# 4_Mosfet.net
KiCad netlist of a schematic drawn in Altium Designer
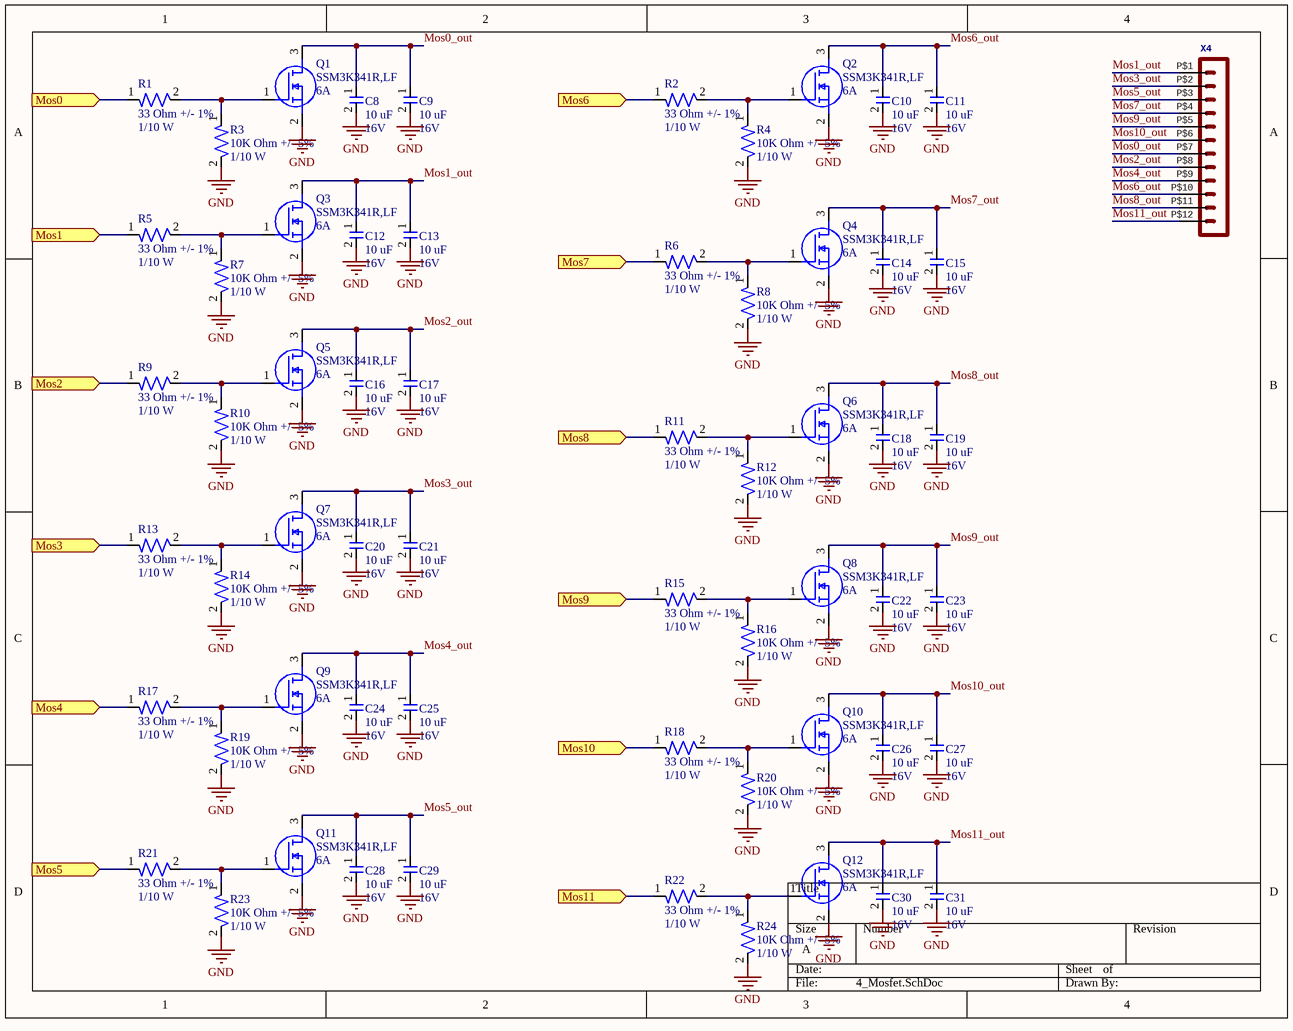
[diagram p0: 4_Mosfet.SchDoc]

(export (version "E")
  (design (tool "Eeschema 10.0.6"))
  (components
    (comp (ref "C8")
      (value "CL21A106KOQNNNE")
      (footprint "CAP-0805")
      (description "10 µF ±10% 16V Ceramic Capacitor X7R 0805 (2012 Metric)")
      (fields (field (name "CAPACITANCE") "10 uF") (field (name "VOLTAGE RATING") "16V"))
      (libsource (lib "MasterLib") (part "CAP-10U-0002"))
    )
    (comp (ref "C9")
      (value "CL21A106KOQNNNE")
      (footprint "CAP-0805")
      (description "10 µF ±10% 16V Ceramic Capacitor X7R 0805 (2012 Metric)")
      (fields (field (name "CAPACITANCE") "10 uF") (field (name "VOLTAGE RATING") "16V"))
      (libsource (lib "MasterLib") (part "CAP-10U-0002"))
    )
    (comp (ref "C10")
      (value "CL21A106KOQNNNE")
      (footprint "CAP-0805")
      (description "10 µF ±10% 16V Ceramic Capacitor X7R 0805 (2012 Metric)")
      (fields (field (name "CAPACITANCE") "10 uF") (field (name "VOLTAGE RATING") "16V"))
      (libsource (lib "MasterLib") (part "CAP-10U-0002"))
    )
    (comp (ref "C11")
      (value "CL21A106KOQNNNE")
      (footprint "CAP-0805")
      (description "10 µF ±10% 16V Ceramic Capacitor X7R 0805 (2012 Metric)")
      (fields (field (name "CAPACITANCE") "10 uF") (field (name "VOLTAGE RATING") "16V"))
      (libsource (lib "MasterLib") (part "CAP-10U-0002"))
    )
    (comp (ref "C12")
      (value "CL21A106KOQNNNE")
      (footprint "CAP-0805")
      (description "10 µF ±10% 16V Ceramic Capacitor X7R 0805 (2012 Metric)")
      (fields (field (name "CAPACITANCE") "10 uF") (field (name "VOLTAGE RATING") "16V"))
      (libsource (lib "MasterLib") (part "CAP-10U-0002"))
    )
    (comp (ref "C13")
      (value "CL21A106KOQNNNE")
      (footprint "CAP-0805")
      (description "10 µF ±10% 16V Ceramic Capacitor X7R 0805 (2012 Metric)")
      (fields (field (name "CAPACITANCE") "10 uF") (field (name "VOLTAGE RATING") "16V"))
      (libsource (lib "MasterLib") (part "CAP-10U-0002"))
    )
    (comp (ref "C14")
      (value "CL21A106KOQNNNE")
      (footprint "CAP-0805")
      (description "10 µF ±10% 16V Ceramic Capacitor X7R 0805 (2012 Metric)")
      (fields (field (name "CAPACITANCE") "10 uF") (field (name "VOLTAGE RATING") "16V"))
      (libsource (lib "MasterLib") (part "CAP-10U-0002"))
    )
    (comp (ref "C15")
      (value "CL21A106KOQNNNE")
      (footprint "CAP-0805")
      (description "10 µF ±10% 16V Ceramic Capacitor X7R 0805 (2012 Metric)")
      (fields (field (name "CAPACITANCE") "10 uF") (field (name "VOLTAGE RATING") "16V"))
      (libsource (lib "MasterLib") (part "CAP-10U-0002"))
    )
    (comp (ref "C16")
      (value "CL21A106KOQNNNE")
      (footprint "CAP-0805")
      (description "10 µF ±10% 16V Ceramic Capacitor X7R 0805 (2012 Metric)")
      (fields (field (name "CAPACITANCE") "10 uF") (field (name "VOLTAGE RATING") "16V"))
      (libsource (lib "MasterLib") (part "CAP-10U-0002"))
    )
    (comp (ref "C17")
      (value "CL21A106KOQNNNE")
      (footprint "CAP-0805")
      (description "10 µF ±10% 16V Ceramic Capacitor X7R 0805 (2012 Metric)")
      (fields (field (name "CAPACITANCE") "10 uF") (field (name "VOLTAGE RATING") "16V"))
      (libsource (lib "MasterLib") (part "CAP-10U-0002"))
    )
    (comp (ref "C18")
      (value "CL21A106KOQNNNE")
      (footprint "CAP-0805")
      (description "10 µF ±10% 16V Ceramic Capacitor X7R 0805 (2012 Metric)")
      (fields (field (name "CAPACITANCE") "10 uF") (field (name "VOLTAGE RATING") "16V"))
      (libsource (lib "MasterLib") (part "CAP-10U-0002"))
    )
    (comp (ref "C19")
      (value "CL21A106KOQNNNE")
      (footprint "CAP-0805")
      (description "10 µF ±10% 16V Ceramic Capacitor X7R 0805 (2012 Metric)")
      (fields (field (name "CAPACITANCE") "10 uF") (field (name "VOLTAGE RATING") "16V"))
      (libsource (lib "MasterLib") (part "CAP-10U-0002"))
    )
    (comp (ref "C20")
      (value "CL21A106KOQNNNE")
      (footprint "CAP-0805")
      (description "10 µF ±10% 16V Ceramic Capacitor X7R 0805 (2012 Metric)")
      (fields (field (name "CAPACITANCE") "10 uF") (field (name "VOLTAGE RATING") "16V"))
      (libsource (lib "MasterLib") (part "CAP-10U-0002"))
    )
    (comp (ref "C21")
      (value "CL21A106KOQNNNE")
      (footprint "CAP-0805")
      (description "10 µF ±10% 16V Ceramic Capacitor X7R 0805 (2012 Metric)")
      (fields (field (name "CAPACITANCE") "10 uF") (field (name "VOLTAGE RATING") "16V"))
      (libsource (lib "MasterLib") (part "CAP-10U-0002"))
    )
    (comp (ref "C22")
      (value "CL21A106KOQNNNE")
      (footprint "CAP-0805")
      (description "10 µF ±10% 16V Ceramic Capacitor X7R 0805 (2012 Metric)")
      (fields (field (name "CAPACITANCE") "10 uF") (field (name "VOLTAGE RATING") "16V"))
      (libsource (lib "MasterLib") (part "CAP-10U-0002"))
    )
    (comp (ref "C23")
      (value "CL21A106KOQNNNE")
      (footprint "CAP-0805")
      (description "10 µF ±10% 16V Ceramic Capacitor X7R 0805 (2012 Metric)")
      (fields (field (name "CAPACITANCE") "10 uF") (field (name "VOLTAGE RATING") "16V"))
      (libsource (lib "MasterLib") (part "CAP-10U-0002"))
    )
    (comp (ref "C24")
      (value "CL21A106KOQNNNE")
      (footprint "CAP-0805")
      (description "10 µF ±10% 16V Ceramic Capacitor X7R 0805 (2012 Metric)")
      (fields (field (name "CAPACITANCE") "10 uF") (field (name "VOLTAGE RATING") "16V"))
      (libsource (lib "MasterLib") (part "CAP-10U-0002"))
    )
    (comp (ref "C25")
      (value "CL21A106KOQNNNE")
      (footprint "CAP-0805")
      (description "10 µF ±10% 16V Ceramic Capacitor X7R 0805 (2012 Metric)")
      (fields (field (name "CAPACITANCE") "10 uF") (field (name "VOLTAGE RATING") "16V"))
      (libsource (lib "MasterLib") (part "CAP-10U-0002"))
    )
    (comp (ref "C26")
      (value "CL21A106KOQNNNE")
      (footprint "CAP-0805")
      (description "10 µF ±10% 16V Ceramic Capacitor X7R 0805 (2012 Metric)")
      (fields (field (name "CAPACITANCE") "10 uF") (field (name "VOLTAGE RATING") "16V"))
      (libsource (lib "MasterLib") (part "CAP-10U-0002"))
    )
    (comp (ref "C27")
      (value "CL21A106KOQNNNE")
      (footprint "CAP-0805")
      (description "10 µF ±10% 16V Ceramic Capacitor X7R 0805 (2012 Metric)")
      (fields (field (name "CAPACITANCE") "10 uF") (field (name "VOLTAGE RATING") "16V"))
      (libsource (lib "MasterLib") (part "CAP-10U-0002"))
    )
    (comp (ref "C28")
      (value "CL21A106KOQNNNE")
      (footprint "CAP-0805")
      (description "10 µF ±10% 16V Ceramic Capacitor X7R 0805 (2012 Metric)")
      (fields (field (name "CAPACITANCE") "10 uF") (field (name "VOLTAGE RATING") "16V"))
      (libsource (lib "MasterLib") (part "CAP-10U-0002"))
    )
    (comp (ref "C29")
      (value "CL21A106KOQNNNE")
      (footprint "CAP-0805")
      (description "10 µF ±10% 16V Ceramic Capacitor X7R 0805 (2012 Metric)")
      (fields (field (name "CAPACITANCE") "10 uF") (field (name "VOLTAGE RATING") "16V"))
      (libsource (lib "MasterLib") (part "CAP-10U-0002"))
    )
    (comp (ref "C30")
      (value "CL21A106KOQNNNE")
      (footprint "CAP-0805")
      (description "10 µF ±10% 16V Ceramic Capacitor X7R 0805 (2012 Metric)")
      (fields (field (name "CAPACITANCE") "10 uF") (field (name "VOLTAGE RATING") "16V"))
      (libsource (lib "MasterLib") (part "CAP-10U-0002"))
    )
    (comp (ref "C31")
      (value "CL21A106KOQNNNE")
      (footprint "CAP-0805")
      (description "10 µF ±10% 16V Ceramic Capacitor X7R 0805 (2012 Metric)")
      (fields (field (name "CAPACITANCE") "10 uF") (field (name "VOLTAGE RATING") "16V"))
      (libsource (lib "MasterLib") (part "CAP-10U-0002"))
    )
    (comp (ref "Q1")
      (value "SSM3K341R,LF")
      (footprint "NMOS-SOT23-3")
      (description "N-Channel 60 V 6A (Ta) 1.2W (Ta) Surface Mount SOT-23F")
      (fields (field (name "ID") "6A"))
      (libsource (lib "MasterLib") (part "NMOS-5A-0001"))
    )
    (comp (ref "Q2")
      (value "SSM3K341R,LF")
      (footprint "NMOS-SOT23-3")
      (description "N-Channel 60 V 6A (Ta) 1.2W (Ta) Surface Mount SOT-23F")
      (fields (field (name "ID") "6A"))
      (libsource (lib "MasterLib") (part "NMOS-5A-0001"))
    )
    (comp (ref "Q3")
      (value "SSM3K341R,LF")
      (footprint "NMOS-SOT23-3")
      (description "N-Channel 60 V 6A (Ta) 1.2W (Ta) Surface Mount SOT-23F")
      (fields (field (name "ID") "6A"))
      (libsource (lib "MasterLib") (part "NMOS-5A-0001"))
    )
    (comp (ref "Q4")
      (value "SSM3K341R,LF")
      (footprint "NMOS-SOT23-3")
      (description "N-Channel 60 V 6A (Ta) 1.2W (Ta) Surface Mount SOT-23F")
      (fields (field (name "ID") "6A"))
      (libsource (lib "MasterLib") (part "NMOS-5A-0001"))
    )
    (comp (ref "Q5")
      (value "SSM3K341R,LF")
      (footprint "NMOS-SOT23-3")
      (description "N-Channel 60 V 6A (Ta) 1.2W (Ta) Surface Mount SOT-23F")
      (fields (field (name "ID") "6A"))
      (libsource (lib "MasterLib") (part "NMOS-5A-0001"))
    )
    (comp (ref "Q6")
      (value "SSM3K341R,LF")
      (footprint "NMOS-SOT23-3")
      (description "N-Channel 60 V 6A (Ta) 1.2W (Ta) Surface Mount SOT-23F")
      (fields (field (name "ID") "6A"))
      (libsource (lib "MasterLib") (part "NMOS-5A-0001"))
    )
    (comp (ref "Q7")
      (value "SSM3K341R,LF")
      (footprint "NMOS-SOT23-3")
      (description "N-Channel 60 V 6A (Ta) 1.2W (Ta) Surface Mount SOT-23F")
      (fields (field (name "ID") "6A"))
      (libsource (lib "MasterLib") (part "NMOS-5A-0001"))
    )
    (comp (ref "Q8")
      (value "SSM3K341R,LF")
      (footprint "NMOS-SOT23-3")
      (description "N-Channel 60 V 6A (Ta) 1.2W (Ta) Surface Mount SOT-23F")
      (fields (field (name "ID") "6A"))
      (libsource (lib "MasterLib") (part "NMOS-5A-0001"))
    )
    (comp (ref "Q9")
      (value "SSM3K341R,LF")
      (footprint "NMOS-SOT23-3")
      (description "N-Channel 60 V 6A (Ta) 1.2W (Ta) Surface Mount SOT-23F")
      (fields (field (name "ID") "6A"))
      (libsource (lib "MasterLib") (part "NMOS-5A-0001"))
    )
    (comp (ref "Q10")
      (value "SSM3K341R,LF")
      (footprint "NMOS-SOT23-3")
      (description "N-Channel 60 V 6A (Ta) 1.2W (Ta) Surface Mount SOT-23F")
      (fields (field (name "ID") "6A"))
      (libsource (lib "MasterLib") (part "NMOS-5A-0001"))
    )
    (comp (ref "Q11")
      (value "SSM3K341R,LF")
      (footprint "NMOS-SOT23-3")
      (description "N-Channel 60 V 6A (Ta) 1.2W (Ta) Surface Mount SOT-23F")
      (fields (field (name "ID") "6A"))
      (libsource (lib "MasterLib") (part "NMOS-5A-0001"))
    )
    (comp (ref "Q12")
      (value "SSM3K341R,LF")
      (footprint "NMOS-SOT23-3")
      (description "N-Channel 60 V 6A (Ta) 1.2W (Ta) Surface Mount SOT-23F")
      (fields (field (name "ID") "6A"))
      (libsource (lib "MasterLib") (part "NMOS-5A-0001"))
    )
    (comp (ref "R1")
      (value "ERJ2RKF33R0X")
      (footprint "RES-0402")
      (description "100mW Thick Film Resistors ±100ppm/℃ ±1% -55℃~+155℃ 33Ω 0402  Chip Resistor - Surface Mount ROHS")
      (fields
        (field (name "RESISTANCE") "33 Ohm +/- 1%")
        (field (name "POWER") "1/10 W")
        (field (name "JLC PART NUMBER") "C278594")
      )
      (libsource (lib "MasterLib") (part "RES-33-0003-JLC"))
    )
    (comp (ref "R2")
      (value "ERJ2RKF33R0X")
      (footprint "RES-0402")
      (description "100mW Thick Film Resistors ±100ppm/℃ ±1% -55℃~+155℃ 33Ω 0402  Chip Resistor - Surface Mount ROHS")
      (fields
        (field (name "RESISTANCE") "33 Ohm +/- 1%")
        (field (name "POWER") "1/10 W")
        (field (name "JLC PART NUMBER") "C278594")
      )
      (libsource (lib "MasterLib") (part "RES-33-0003-JLC"))
    )
    (comp (ref "R3")
      (value "ERJ2GEJ103X")
      (footprint "RES-0402")
      (fields
        (field (name "RESISTANCE") "10K Ohm +/- 5%")
        (field (name "POWER") "1/10 W")
        (field (name "JLC PART NUMBER") "C278577")
      )
      (libsource (lib "MasterLib") (part "RES-10K-0003-JLC"))
    )
    (comp (ref "R4")
      (value "ERJ2GEJ103X")
      (footprint "RES-0402")
      (fields
        (field (name "RESISTANCE") "10K Ohm +/- 5%")
        (field (name "POWER") "1/10 W")
        (field (name "JLC PART NUMBER") "C278577")
      )
      (libsource (lib "MasterLib") (part "RES-10K-0003-JLC"))
    )
    (comp (ref "R5")
      (value "ERJ2RKF33R0X")
      (footprint "RES-0402")
      (description "100mW Thick Film Resistors ±100ppm/℃ ±1% -55℃~+155℃ 33Ω 0402  Chip Resistor - Surface Mount ROHS")
      (fields
        (field (name "RESISTANCE") "33 Ohm +/- 1%")
        (field (name "POWER") "1/10 W")
        (field (name "JLC PART NUMBER") "C278594")
      )
      (libsource (lib "MasterLib") (part "RES-33-0003-JLC"))
    )
    (comp (ref "R6")
      (value "ERJ2RKF33R0X")
      (footprint "RES-0402")
      (description "100mW Thick Film Resistors ±100ppm/℃ ±1% -55℃~+155℃ 33Ω 0402  Chip Resistor - Surface Mount ROHS")
      (fields
        (field (name "RESISTANCE") "33 Ohm +/- 1%")
        (field (name "POWER") "1/10 W")
        (field (name "JLC PART NUMBER") "C278594")
      )
      (libsource (lib "MasterLib") (part "RES-33-0003-JLC"))
    )
    (comp (ref "R7")
      (value "ERJ2GEJ103X")
      (footprint "RES-0402")
      (fields
        (field (name "RESISTANCE") "10K Ohm +/- 5%")
        (field (name "POWER") "1/10 W")
        (field (name "JLC PART NUMBER") "C278577")
      )
      (libsource (lib "MasterLib") (part "RES-10K-0003-JLC"))
    )
    (comp (ref "R8")
      (value "ERJ2GEJ103X")
      (footprint "RES-0402")
      (fields
        (field (name "RESISTANCE") "10K Ohm +/- 5%")
        (field (name "POWER") "1/10 W")
        (field (name "JLC PART NUMBER") "C278577")
      )
      (libsource (lib "MasterLib") (part "RES-10K-0003-JLC"))
    )
    (comp (ref "R9")
      (value "ERJ2RKF33R0X")
      (footprint "RES-0402")
      (description "100mW Thick Film Resistors ±100ppm/℃ ±1% -55℃~+155℃ 33Ω 0402  Chip Resistor - Surface Mount ROHS")
      (fields
        (field (name "RESISTANCE") "33 Ohm +/- 1%")
        (field (name "POWER") "1/10 W")
        (field (name "JLC PART NUMBER") "C278594")
      )
      (libsource (lib "MasterLib") (part "RES-33-0003-JLC"))
    )
    (comp (ref "R10")
      (value "ERJ2GEJ103X")
      (footprint "RES-0402")
      (fields
        (field (name "RESISTANCE") "10K Ohm +/- 5%")
        (field (name "POWER") "1/10 W")
        (field (name "JLC PART NUMBER") "C278577")
      )
      (libsource (lib "MasterLib") (part "RES-10K-0003-JLC"))
    )
    (comp (ref "R11")
      (value "ERJ2RKF33R0X")
      (footprint "RES-0402")
      (description "100mW Thick Film Resistors ±100ppm/℃ ±1% -55℃~+155℃ 33Ω 0402  Chip Resistor - Surface Mount ROHS")
      (fields
        (field (name "RESISTANCE") "33 Ohm +/- 1%")
        (field (name "POWER") "1/10 W")
        (field (name "JLC PART NUMBER") "C278594")
      )
      (libsource (lib "MasterLib") (part "RES-33-0003-JLC"))
    )
    (comp (ref "R12")
      (value "ERJ2GEJ103X")
      (footprint "RES-0402")
      (fields
        (field (name "RESISTANCE") "10K Ohm +/- 5%")
        (field (name "POWER") "1/10 W")
        (field (name "JLC PART NUMBER") "C278577")
      )
      (libsource (lib "MasterLib") (part "RES-10K-0003-JLC"))
    )
    (comp (ref "R13")
      (value "ERJ2RKF33R0X")
      (footprint "RES-0402")
      (description "100mW Thick Film Resistors ±100ppm/℃ ±1% -55℃~+155℃ 33Ω 0402  Chip Resistor - Surface Mount ROHS")
      (fields
        (field (name "RESISTANCE") "33 Ohm +/- 1%")
        (field (name "POWER") "1/10 W")
        (field (name "JLC PART NUMBER") "C278594")
      )
      (libsource (lib "MasterLib") (part "RES-33-0003-JLC"))
    )
    (comp (ref "R14")
      (value "ERJ2GEJ103X")
      (footprint "RES-0402")
      (fields
        (field (name "RESISTANCE") "10K Ohm +/- 5%")
        (field (name "POWER") "1/10 W")
        (field (name "JLC PART NUMBER") "C278577")
      )
      (libsource (lib "MasterLib") (part "RES-10K-0003-JLC"))
    )
    (comp (ref "R15")
      (value "ERJ2RKF33R0X")
      (footprint "RES-0402")
      (description "100mW Thick Film Resistors ±100ppm/℃ ±1% -55℃~+155℃ 33Ω 0402  Chip Resistor - Surface Mount ROHS")
      (fields
        (field (name "RESISTANCE") "33 Ohm +/- 1%")
        (field (name "POWER") "1/10 W")
        (field (name "JLC PART NUMBER") "C278594")
      )
      (libsource (lib "MasterLib") (part "RES-33-0003-JLC"))
    )
    (comp (ref "R16")
      (value "ERJ2GEJ103X")
      (footprint "RES-0402")
      (fields
        (field (name "RESISTANCE") "10K Ohm +/- 5%")
        (field (name "POWER") "1/10 W")
        (field (name "JLC PART NUMBER") "C278577")
      )
      (libsource (lib "MasterLib") (part "RES-10K-0003-JLC"))
    )
    (comp (ref "R17")
      (value "ERJ2RKF33R0X")
      (footprint "RES-0402")
      (description "100mW Thick Film Resistors ±100ppm/℃ ±1% -55℃~+155℃ 33Ω 0402  Chip Resistor - Surface Mount ROHS")
      (fields
        (field (name "RESISTANCE") "33 Ohm +/- 1%")
        (field (name "POWER") "1/10 W")
        (field (name "JLC PART NUMBER") "C278594")
      )
      (libsource (lib "MasterLib") (part "RES-33-0003-JLC"))
    )
    (comp (ref "R18")
      (value "ERJ2RKF33R0X")
      (footprint "RES-0402")
      (description "100mW Thick Film Resistors ±100ppm/℃ ±1% -55℃~+155℃ 33Ω 0402  Chip Resistor - Surface Mount ROHS")
      (fields
        (field (name "RESISTANCE") "33 Ohm +/- 1%")
        (field (name "POWER") "1/10 W")
        (field (name "JLC PART NUMBER") "C278594")
      )
      (libsource (lib "MasterLib") (part "RES-33-0003-JLC"))
    )
    (comp (ref "R19")
      (value "ERJ2GEJ103X")
      (footprint "RES-0402")
      (fields
        (field (name "RESISTANCE") "10K Ohm +/- 5%")
        (field (name "POWER") "1/10 W")
        (field (name "JLC PART NUMBER") "C278577")
      )
      (libsource (lib "MasterLib") (part "RES-10K-0003-JLC"))
    )
    (comp (ref "R20")
      (value "ERJ2GEJ103X")
      (footprint "RES-0402")
      (fields
        (field (name "RESISTANCE") "10K Ohm +/- 5%")
        (field (name "POWER") "1/10 W")
        (field (name "JLC PART NUMBER") "C278577")
      )
      (libsource (lib "MasterLib") (part "RES-10K-0003-JLC"))
    )
    (comp (ref "R21")
      (value "ERJ2RKF33R0X")
      (footprint "RES-0402")
      (description "100mW Thick Film Resistors ±100ppm/℃ ±1% -55℃~+155℃ 33Ω 0402  Chip Resistor - Surface Mount ROHS")
      (fields
        (field (name "RESISTANCE") "33 Ohm +/- 1%")
        (field (name "POWER") "1/10 W")
        (field (name "JLC PART NUMBER") "C278594")
      )
      (libsource (lib "MasterLib") (part "RES-33-0003-JLC"))
    )
    (comp (ref "R22")
      (value "ERJ2RKF33R0X")
      (footprint "RES-0402")
      (description "100mW Thick Film Resistors ±100ppm/℃ ±1% -55℃~+155℃ 33Ω 0402  Chip Resistor - Surface Mount ROHS")
      (fields
        (field (name "RESISTANCE") "33 Ohm +/- 1%")
        (field (name "POWER") "1/10 W")
        (field (name "JLC PART NUMBER") "C278594")
      )
      (libsource (lib "MasterLib") (part "RES-33-0003-JLC"))
    )
    (comp (ref "R23")
      (value "ERJ2GEJ103X")
      (footprint "RES-0402")
      (fields
        (field (name "RESISTANCE") "10K Ohm +/- 5%")
        (field (name "POWER") "1/10 W")
        (field (name "JLC PART NUMBER") "C278577")
      )
      (libsource (lib "MasterLib") (part "RES-10K-0003-JLC"))
    )
    (comp (ref "R24")
      (value "ERJ2GEJ103X")
      (footprint "RES-0402")
      (fields
        (field (name "RESISTANCE") "10K Ohm +/- 5%")
        (field (name "POWER") "1/10 W")
        (field (name "JLC PART NUMBER") "C278577")
      )
      (libsource (lib "MasterLib") (part "RES-10K-0003-JLC"))
    )
    (comp (ref "X4")
      (value "Molex - Micro-Fit 3.0 Series connector,  3.00mm (0.118\") pitch header, 12 positions.")
      (footprint "43045-1212")
      (libsource (lib "Molex Microfit") (part "HEADER_POS12_?43045-1212"))
    )
  )
  (nets
    (net (code "1") (name "/Mos0") (class "Default")
      (node (ref "R1") (pin "1") (pinfunction "1_1") (pintype "passive"))
    )
    (net (code "2") (name "/Mos0_out") (class "Default")
      (node (ref "C8") (pin "1") (pinfunction "1_1") (pintype "passive"))
      (node (ref "C9") (pin "1") (pinfunction "1_1") (pintype "passive"))
      (node (ref "Q1") (pin "3") (pinfunction "D_3") (pintype "passive"))
      (node (ref "X4") (pin "P$7") (pinfunction "7_P$7") (pintype "passive"))
    )
    (net (code "3") (name "/Mos1") (class "Default")
      (node (ref "R5") (pin "1") (pinfunction "1_1") (pintype "passive"))
    )
    (net (code "4") (name "/Mos1_out") (class "Default")
      (node (ref "C12") (pin "1") (pinfunction "1_1") (pintype "passive"))
      (node (ref "C13") (pin "1") (pinfunction "1_1") (pintype "passive"))
      (node (ref "Q3") (pin "3") (pinfunction "D_3") (pintype "passive"))
      (node (ref "X4") (pin "P$1") (pinfunction "1_P$1") (pintype "passive"))
    )
    (net (code "5") (name "/Mos2") (class "Default")
      (node (ref "R9") (pin "1") (pinfunction "1_1") (pintype "passive"))
    )
    (net (code "6") (name "/Mos2_out") (class "Default")
      (node (ref "C16") (pin "1") (pinfunction "1_1") (pintype "passive"))
      (node (ref "C17") (pin "1") (pinfunction "1_1") (pintype "passive"))
      (node (ref "Q5") (pin "3") (pinfunction "D_3") (pintype "passive"))
      (node (ref "X4") (pin "P$8") (pinfunction "8_P$8") (pintype "passive"))
    )
    (net (code "7") (name "/Mos3") (class "Default")
      (node (ref "R13") (pin "1") (pinfunction "1_1") (pintype "passive"))
    )
    (net (code "8") (name "/Mos3_out") (class "Default")
      (node (ref "C20") (pin "1") (pinfunction "1_1") (pintype "passive"))
      (node (ref "C21") (pin "1") (pinfunction "1_1") (pintype "passive"))
      (node (ref "Q7") (pin "3") (pinfunction "D_3") (pintype "passive"))
      (node (ref "X4") (pin "P$2") (pinfunction "2_P$2") (pintype "passive"))
    )
    (net (code "9") (name "/Mos4") (class "Default")
      (node (ref "R17") (pin "1") (pinfunction "1_1") (pintype "passive"))
    )
    (net (code "10") (name "/Mos4_out") (class "Default")
      (node (ref "C24") (pin "1") (pinfunction "1_1") (pintype "passive"))
      (node (ref "C25") (pin "1") (pinfunction "1_1") (pintype "passive"))
      (node (ref "Q9") (pin "3") (pinfunction "D_3") (pintype "passive"))
      (node (ref "X4") (pin "P$9") (pinfunction "9_P$9") (pintype "passive"))
    )
    (net (code "11") (name "/Mos5") (class "Default")
      (node (ref "R21") (pin "1") (pinfunction "1_1") (pintype "passive"))
    )
    (net (code "12") (name "/Mos5_out") (class "Default")
      (node (ref "C28") (pin "1") (pinfunction "1_1") (pintype "passive"))
      (node (ref "C29") (pin "1") (pinfunction "1_1") (pintype "passive"))
      (node (ref "Q11") (pin "3") (pinfunction "D_3") (pintype "passive"))
      (node (ref "X4") (pin "P$3") (pinfunction "3_P$3") (pintype "passive"))
    )
    (net (code "13") (name "/Mos6") (class "Default")
      (node (ref "R2") (pin "1") (pinfunction "1_1") (pintype "passive"))
    )
    (net (code "14") (name "/Mos6_out") (class "Default")
      (node (ref "C10") (pin "1") (pinfunction "1_1") (pintype "passive"))
      (node (ref "C11") (pin "1") (pinfunction "1_1") (pintype "passive"))
      (node (ref "Q2") (pin "3") (pinfunction "D_3") (pintype "passive"))
      (node (ref "X4") (pin "P$10") (pinfunction "10_P$10") (pintype "passive"))
    )
    (net (code "15") (name "/Mos7") (class "Default")
      (node (ref "R6") (pin "1") (pinfunction "1_1") (pintype "passive"))
    )
    (net (code "16") (name "/Mos7_out") (class "Default")
      (node (ref "C14") (pin "1") (pinfunction "1_1") (pintype "passive"))
      (node (ref "C15") (pin "1") (pinfunction "1_1") (pintype "passive"))
      (node (ref "Q4") (pin "3") (pinfunction "D_3") (pintype "passive"))
      (node (ref "X4") (pin "P$4") (pinfunction "4_P$4") (pintype "passive"))
    )
    (net (code "17") (name "/Mos8") (class "Default")
      (node (ref "R11") (pin "1") (pinfunction "1_1") (pintype "passive"))
    )
    (net (code "18") (name "/Mos8_out") (class "Default")
      (node (ref "C18") (pin "1") (pinfunction "1_1") (pintype "passive"))
      (node (ref "C19") (pin "1") (pinfunction "1_1") (pintype "passive"))
      (node (ref "Q6") (pin "3") (pinfunction "D_3") (pintype "passive"))
      (node (ref "X4") (pin "P$11") (pinfunction "11_P$11") (pintype "passive"))
    )
    (net (code "19") (name "/Mos9") (class "Default")
      (node (ref "R15") (pin "1") (pinfunction "1_1") (pintype "passive"))
    )
    (net (code "20") (name "/Mos9_out") (class "Default")
      (node (ref "C22") (pin "1") (pinfunction "1_1") (pintype "passive"))
      (node (ref "C23") (pin "1") (pinfunction "1_1") (pintype "passive"))
      (node (ref "Q8") (pin "3") (pinfunction "D_3") (pintype "passive"))
      (node (ref "X4") (pin "P$5") (pinfunction "5_P$5") (pintype "passive"))
    )
    (net (code "21") (name "/Mos10") (class "Default")
      (node (ref "R18") (pin "1") (pinfunction "1_1") (pintype "passive"))
    )
    (net (code "22") (name "/Mos10_out") (class "Default")
      (node (ref "C26") (pin "1") (pinfunction "1_1") (pintype "passive"))
      (node (ref "C27") (pin "1") (pinfunction "1_1") (pintype "passive"))
      (node (ref "Q10") (pin "3") (pinfunction "D_3") (pintype "passive"))
      (node (ref "X4") (pin "P$6") (pinfunction "6_P$6") (pintype "passive"))
    )
    (net (code "23") (name "/Mos11") (class "Default")
      (node (ref "R22") (pin "1") (pinfunction "1_1") (pintype "passive"))
    )
    (net (code "24") (name "/Mos11_out") (class "Default")
      (node (ref "C30") (pin "1") (pinfunction "1_1") (pintype "passive"))
      (node (ref "C31") (pin "1") (pinfunction "1_1") (pintype "passive"))
      (node (ref "Q12") (pin "3") (pinfunction "D_3") (pintype "passive"))
      (node (ref "X4") (pin "P$12") (pinfunction "12_P$12") (pintype "passive"))
    )
    (net (code "25") (name "GND") (class "Default")
      (node (ref "C10") (pin "2") (pinfunction "2_2") (pintype "passive"))
      (node (ref "C11") (pin "2") (pinfunction "2_2") (pintype "passive"))
      (node (ref "C12") (pin "2") (pinfunction "2_2") (pintype "passive"))
      (node (ref "C13") (pin "2") (pinfunction "2_2") (pintype "passive"))
      (node (ref "C14") (pin "2") (pinfunction "2_2") (pintype "passive"))
      (node (ref "C15") (pin "2") (pinfunction "2_2") (pintype "passive"))
      (node (ref "C16") (pin "2") (pinfunction "2_2") (pintype "passive"))
      (node (ref "C17") (pin "2") (pinfunction "2_2") (pintype "passive"))
      (node (ref "C18") (pin "2") (pinfunction "2_2") (pintype "passive"))
      (node (ref "C19") (pin "2") (pinfunction "2_2") (pintype "passive"))
      (node (ref "C20") (pin "2") (pinfunction "2_2") (pintype "passive"))
      (node (ref "C21") (pin "2") (pinfunction "2_2") (pintype "passive"))
      (node (ref "C22") (pin "2") (pinfunction "2_2") (pintype "passive"))
      (node (ref "C23") (pin "2") (pinfunction "2_2") (pintype "passive"))
      (node (ref "C24") (pin "2") (pinfunction "2_2") (pintype "passive"))
      (node (ref "C25") (pin "2") (pinfunction "2_2") (pintype "passive"))
      (node (ref "C26") (pin "2") (pinfunction "2_2") (pintype "passive"))
      (node (ref "C27") (pin "2") (pinfunction "2_2") (pintype "passive"))
      (node (ref "C28") (pin "2") (pinfunction "2_2") (pintype "passive"))
      (node (ref "C29") (pin "2") (pinfunction "2_2") (pintype "passive"))
      (node (ref "C30") (pin "2") (pinfunction "2_2") (pintype "passive"))
      (node (ref "C31") (pin "2") (pinfunction "2_2") (pintype "passive"))
      (node (ref "C8") (pin "2") (pinfunction "2_2") (pintype "passive"))
      (node (ref "C9") (pin "2") (pinfunction "2_2") (pintype "passive"))
      (node (ref "Q1") (pin "2") (pinfunction "S_2") (pintype "passive"))
      (node (ref "Q10") (pin "2") (pinfunction "S_2") (pintype "passive"))
      (node (ref "Q11") (pin "2") (pinfunction "S_2") (pintype "passive"))
      (node (ref "Q12") (pin "2") (pinfunction "S_2") (pintype "passive"))
      (node (ref "Q2") (pin "2") (pinfunction "S_2") (pintype "passive"))
      (node (ref "Q3") (pin "2") (pinfunction "S_2") (pintype "passive"))
      (node (ref "Q4") (pin "2") (pinfunction "S_2") (pintype "passive"))
      (node (ref "Q5") (pin "2") (pinfunction "S_2") (pintype "passive"))
      (node (ref "Q6") (pin "2") (pinfunction "S_2") (pintype "passive"))
      (node (ref "Q7") (pin "2") (pinfunction "S_2") (pintype "passive"))
      (node (ref "Q8") (pin "2") (pinfunction "S_2") (pintype "passive"))
      (node (ref "Q9") (pin "2") (pinfunction "S_2") (pintype "passive"))
      (node (ref "R10") (pin "2") (pinfunction "2_2") (pintype "passive"))
      (node (ref "R12") (pin "2") (pinfunction "2_2") (pintype "passive"))
      (node (ref "R14") (pin "2") (pinfunction "2_2") (pintype "passive"))
      (node (ref "R16") (pin "2") (pinfunction "2_2") (pintype "passive"))
      (node (ref "R19") (pin "2") (pinfunction "2_2") (pintype "passive"))
      (node (ref "R20") (pin "2") (pinfunction "2_2") (pintype "passive"))
      (node (ref "R23") (pin "2") (pinfunction "2_2") (pintype "passive"))
      (node (ref "R24") (pin "2") (pinfunction "2_2") (pintype "passive"))
      (node (ref "R3") (pin "2") (pinfunction "2_2") (pintype "passive"))
      (node (ref "R4") (pin "2") (pinfunction "2_2") (pintype "passive"))
      (node (ref "R7") (pin "2") (pinfunction "2_2") (pintype "passive"))
      (node (ref "R8") (pin "2") (pinfunction "2_2") (pintype "passive"))
    )
    (net (code "26") (name "Net-(Q1-G)") (class "Default")
      (node (ref "Q1") (pin "1") (pinfunction "G_1") (pintype "passive"))
      (node (ref "R1") (pin "2") (pinfunction "2_2") (pintype "passive"))
      (node (ref "R3") (pin "1") (pinfunction "1_1") (pintype "passive"))
    )
    (net (code "27") (name "Net-(Q2-G)") (class "Default")
      (node (ref "Q2") (pin "1") (pinfunction "G_1") (pintype "passive"))
      (node (ref "R2") (pin "2") (pinfunction "2_2") (pintype "passive"))
      (node (ref "R4") (pin "1") (pinfunction "1_1") (pintype "passive"))
    )
    (net (code "28") (name "Net-(Q3-G)") (class "Default")
      (node (ref "Q3") (pin "1") (pinfunction "G_1") (pintype "passive"))
      (node (ref "R5") (pin "2") (pinfunction "2_2") (pintype "passive"))
      (node (ref "R7") (pin "1") (pinfunction "1_1") (pintype "passive"))
    )
    (net (code "29") (name "Net-(Q4-G)") (class "Default")
      (node (ref "Q4") (pin "1") (pinfunction "G_1") (pintype "passive"))
      (node (ref "R6") (pin "2") (pinfunction "2_2") (pintype "passive"))
      (node (ref "R8") (pin "1") (pinfunction "1_1") (pintype "passive"))
    )
    (net (code "30") (name "Net-(Q5-G)") (class "Default")
      (node (ref "Q5") (pin "1") (pinfunction "G_1") (pintype "passive"))
      (node (ref "R10") (pin "1") (pinfunction "1_1") (pintype "passive"))
      (node (ref "R9") (pin "2") (pinfunction "2_2") (pintype "passive"))
    )
    (net (code "31") (name "Net-(Q6-G)") (class "Default")
      (node (ref "Q6") (pin "1") (pinfunction "G_1") (pintype "passive"))
      (node (ref "R11") (pin "2") (pinfunction "2_2") (pintype "passive"))
      (node (ref "R12") (pin "1") (pinfunction "1_1") (pintype "passive"))
    )
    (net (code "32") (name "Net-(Q7-G)") (class "Default")
      (node (ref "Q7") (pin "1") (pinfunction "G_1") (pintype "passive"))
      (node (ref "R13") (pin "2") (pinfunction "2_2") (pintype "passive"))
      (node (ref "R14") (pin "1") (pinfunction "1_1") (pintype "passive"))
    )
    (net (code "33") (name "Net-(Q8-G)") (class "Default")
      (node (ref "Q8") (pin "1") (pinfunction "G_1") (pintype "passive"))
      (node (ref "R15") (pin "2") (pinfunction "2_2") (pintype "passive"))
      (node (ref "R16") (pin "1") (pinfunction "1_1") (pintype "passive"))
    )
    (net (code "34") (name "Net-(Q9-G)") (class "Default")
      (node (ref "Q9") (pin "1") (pinfunction "G_1") (pintype "passive"))
      (node (ref "R17") (pin "2") (pinfunction "2_2") (pintype "passive"))
      (node (ref "R19") (pin "1") (pinfunction "1_1") (pintype "passive"))
    )
    (net (code "35") (name "Net-(Q10-G)") (class "Default")
      (node (ref "Q10") (pin "1") (pinfunction "G_1") (pintype "passive"))
      (node (ref "R18") (pin "2") (pinfunction "2_2") (pintype "passive"))
      (node (ref "R20") (pin "1") (pinfunction "1_1") (pintype "passive"))
    )
    (net (code "36") (name "Net-(Q11-G)") (class "Default")
      (node (ref "Q11") (pin "1") (pinfunction "G_1") (pintype "passive"))
      (node (ref "R21") (pin "2") (pinfunction "2_2") (pintype "passive"))
      (node (ref "R23") (pin "1") (pinfunction "1_1") (pintype "passive"))
    )
    (net (code "37") (name "Net-(Q12-G)") (class "Default")
      (node (ref "Q12") (pin "1") (pinfunction "G_1") (pintype "passive"))
      (node (ref "R22") (pin "2") (pinfunction "2_2") (pintype "passive"))
      (node (ref "R24") (pin "1") (pinfunction "1_1") (pintype "passive"))
    )
  )
)
